# 5V_AC-DC_Convertor.net
KiCad netlist of a schematic drawn in EAGLE
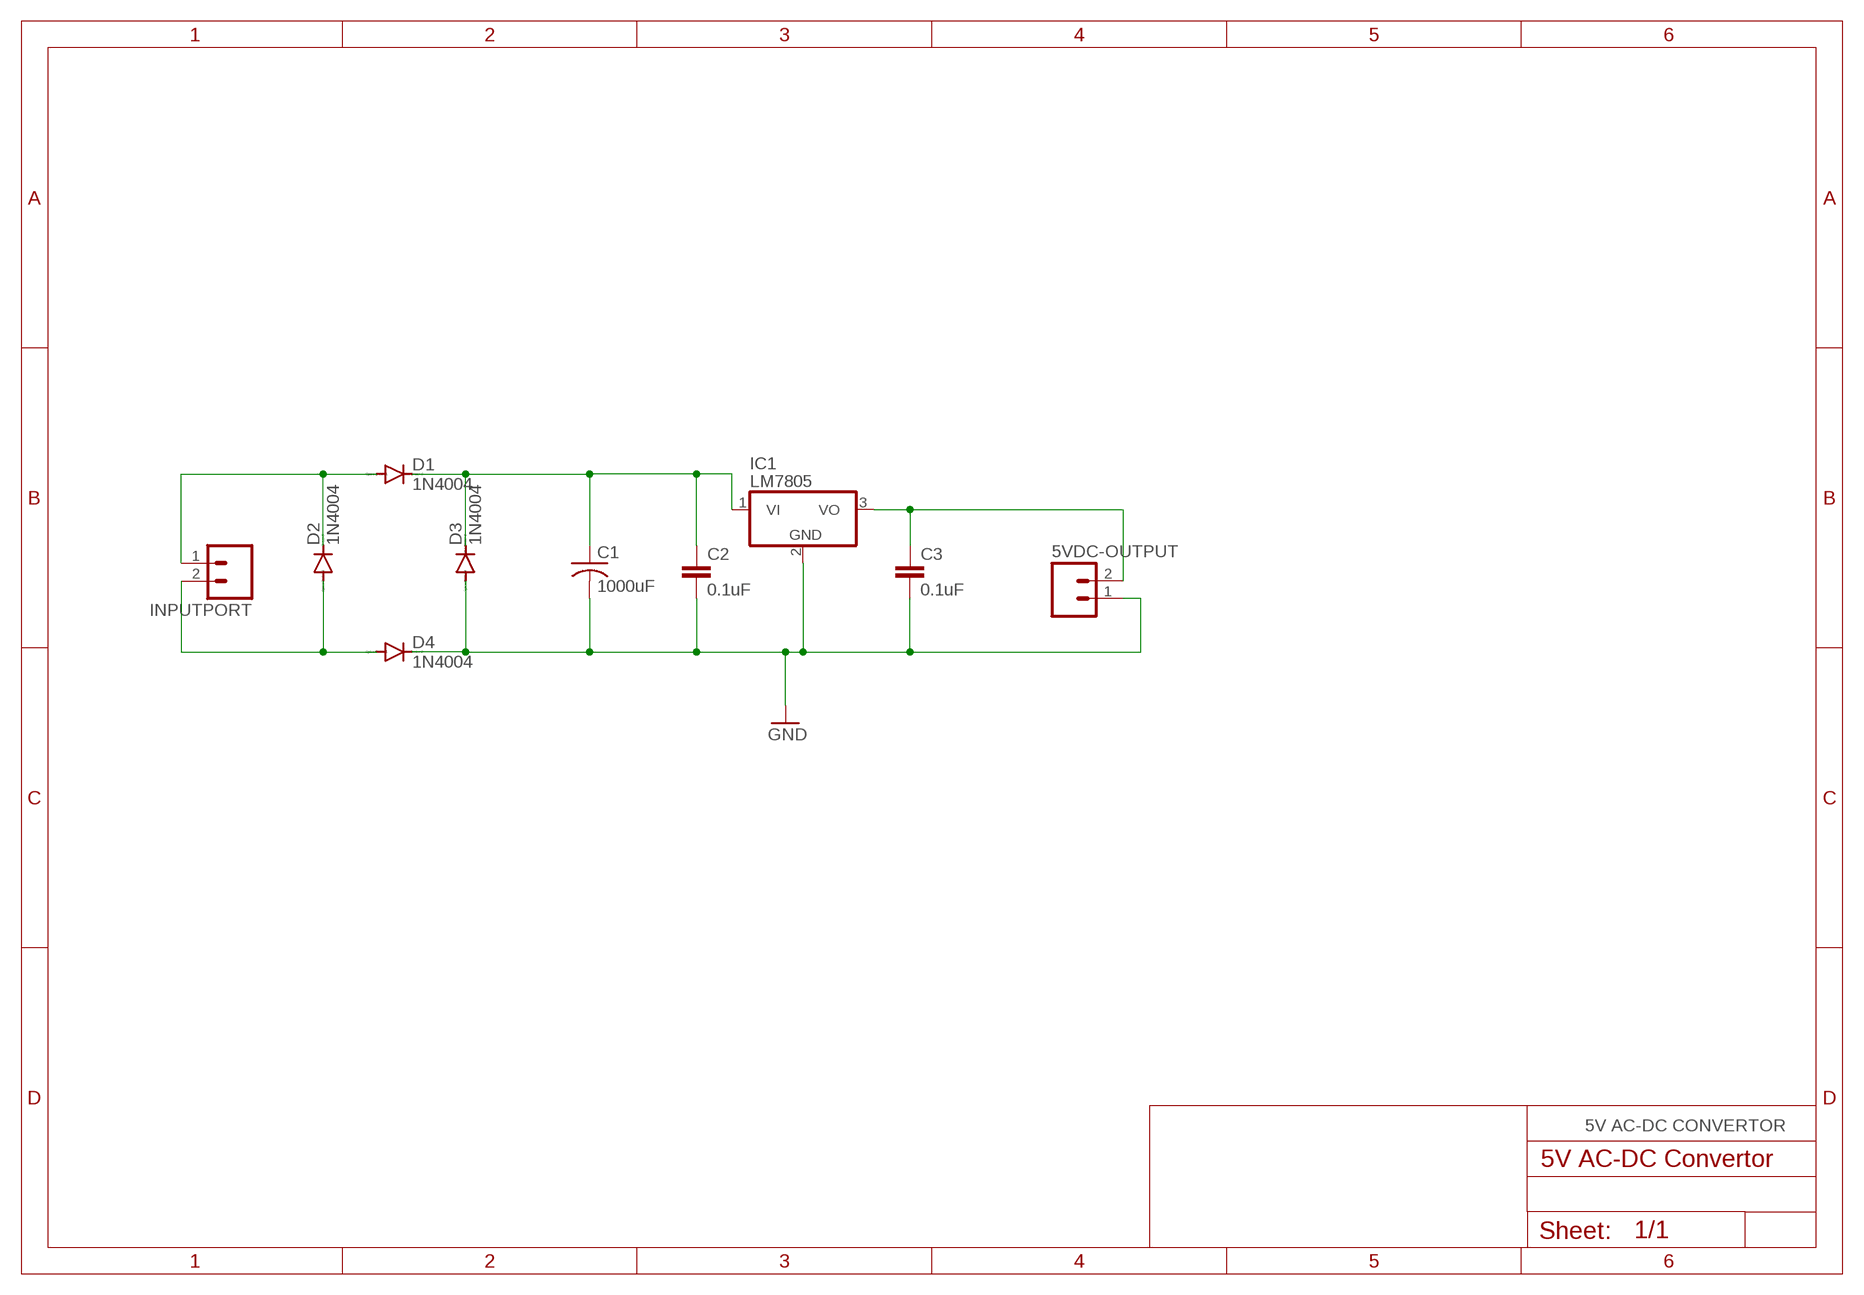
[diagram p0: schematic, sheet 1]

(export (version "E")
  (design (tool "Eeschema 10.0.6"))
  (components
    (comp (ref "5VDC-OUTPUT")
      (value "M02")
      (footprint "eagle-import:02P")
      (libsource (lib "eagle-import") (part "M02"))
    )
    (comp (ref "C1")
      (value "1000uF")
      (footprint "eagle-import:C025-024X044")
      (libsource (lib "eagle-import") (part "C-US025-024X044"))
    )
    (comp (ref "C2")
      (value "0.1uF")
      (footprint "eagle-import:C025-025X050")
      (libsource (lib "eagle-import") (part "C-EU025-025X050"))
    )
    (comp (ref "C3")
      (value "0.1uF")
      (footprint "eagle-import:C025-025X050")
      (libsource (lib "eagle-import") (part "C-EU025-025X050"))
    )
    (comp (ref "D1")
      (value "1N4004")
      (footprint "eagle-import:DO41-10")
      (libsource (lib "eagle-import") (part "1N4004"))
    )
    (comp (ref "D2")
      (value "1N4004")
      (footprint "eagle-import:DO41-10")
      (libsource (lib "eagle-import") (part "1N4004"))
    )
    (comp (ref "D3")
      (value "1N4004")
      (footprint "eagle-import:DO41-10")
      (libsource (lib "eagle-import") (part "1N4004"))
    )
    (comp (ref "D4")
      (value "1N4004")
      (footprint "eagle-import:DO41-10")
      (libsource (lib "eagle-import") (part "1N4004"))
    )
    (comp (ref "IC1")
      (value "LM7805")
      (footprint "eagle-import:TO220V")
      (libsource (lib "eagle-import") (part "78TV6"))
    )
    (comp (ref "INPUTPORT")
      (value "M02")
      (footprint "eagle-import:02P")
      (libsource (lib "eagle-import") (part "M02"))
    )
  )
  (nets
    (net (code "1") (name "GND") (class "Default")
      (node (ref "5VDC-OUTPUT") (pin "1") (pinfunction "1_1") (pintype "passive"))
      (node (ref "C1") (pin "2") (pinfunction "2_2") (pintype "passive"))
      (node (ref "C2") (pin "2") (pinfunction "2_2") (pintype "passive"))
      (node (ref "C3") (pin "2") (pinfunction "2_2") (pintype "passive"))
      (node (ref "D3") (pin "A") (pinfunction "A_A") (pintype "passive"))
      (node (ref "D4") (pin "C") (pinfunction "C_C") (pintype "passive"))
      (node (ref "IC1") (pin "2") (pinfunction "GND_2") (pintype "passive"))
    )
    (net (code "2") (name "Net-(D1-PadA)") (class "Default")
      (node (ref "D1") (pin "A") (pinfunction "A_A") (pintype "passive"))
      (node (ref "D2") (pin "C") (pinfunction "C_C") (pintype "passive"))
      (node (ref "INPUTPORT") (pin "1") (pinfunction "1_1") (pintype "passive"))
    )
    (net (code "3") (name "Net-(D2-PadA)") (class "Default")
      (node (ref "D2") (pin "A") (pinfunction "A_A") (pintype "passive"))
      (node (ref "D4") (pin "A") (pinfunction "A_A") (pintype "passive"))
      (node (ref "INPUTPORT") (pin "2") (pinfunction "2_2") (pintype "passive"))
    )
    (net (code "4") (name "Net-(IC1-VI)") (class "Default")
      (node (ref "C1") (pin "1") (pinfunction "1_1") (pintype "passive"))
      (node (ref "C2") (pin "1") (pinfunction "1_1") (pintype "passive"))
      (node (ref "D1") (pin "C") (pinfunction "C_C") (pintype "passive"))
      (node (ref "D3") (pin "C") (pinfunction "C_C") (pintype "passive"))
      (node (ref "IC1") (pin "1") (pinfunction "VI_1") (pintype "input"))
    )
    (net (code "5") (name "Net-(IC1-VO)") (class "Default")
      (node (ref "5VDC-OUTPUT") (pin "2") (pinfunction "2_2") (pintype "passive"))
      (node (ref "C3") (pin "1") (pinfunction "1_1") (pintype "passive"))
      (node (ref "IC1") (pin "3") (pinfunction "VO_3") (pintype "passive"))
    )
  )
)
